# Color_Sensor.net
KiCad netlist of a schematic drawn in Altium Designer
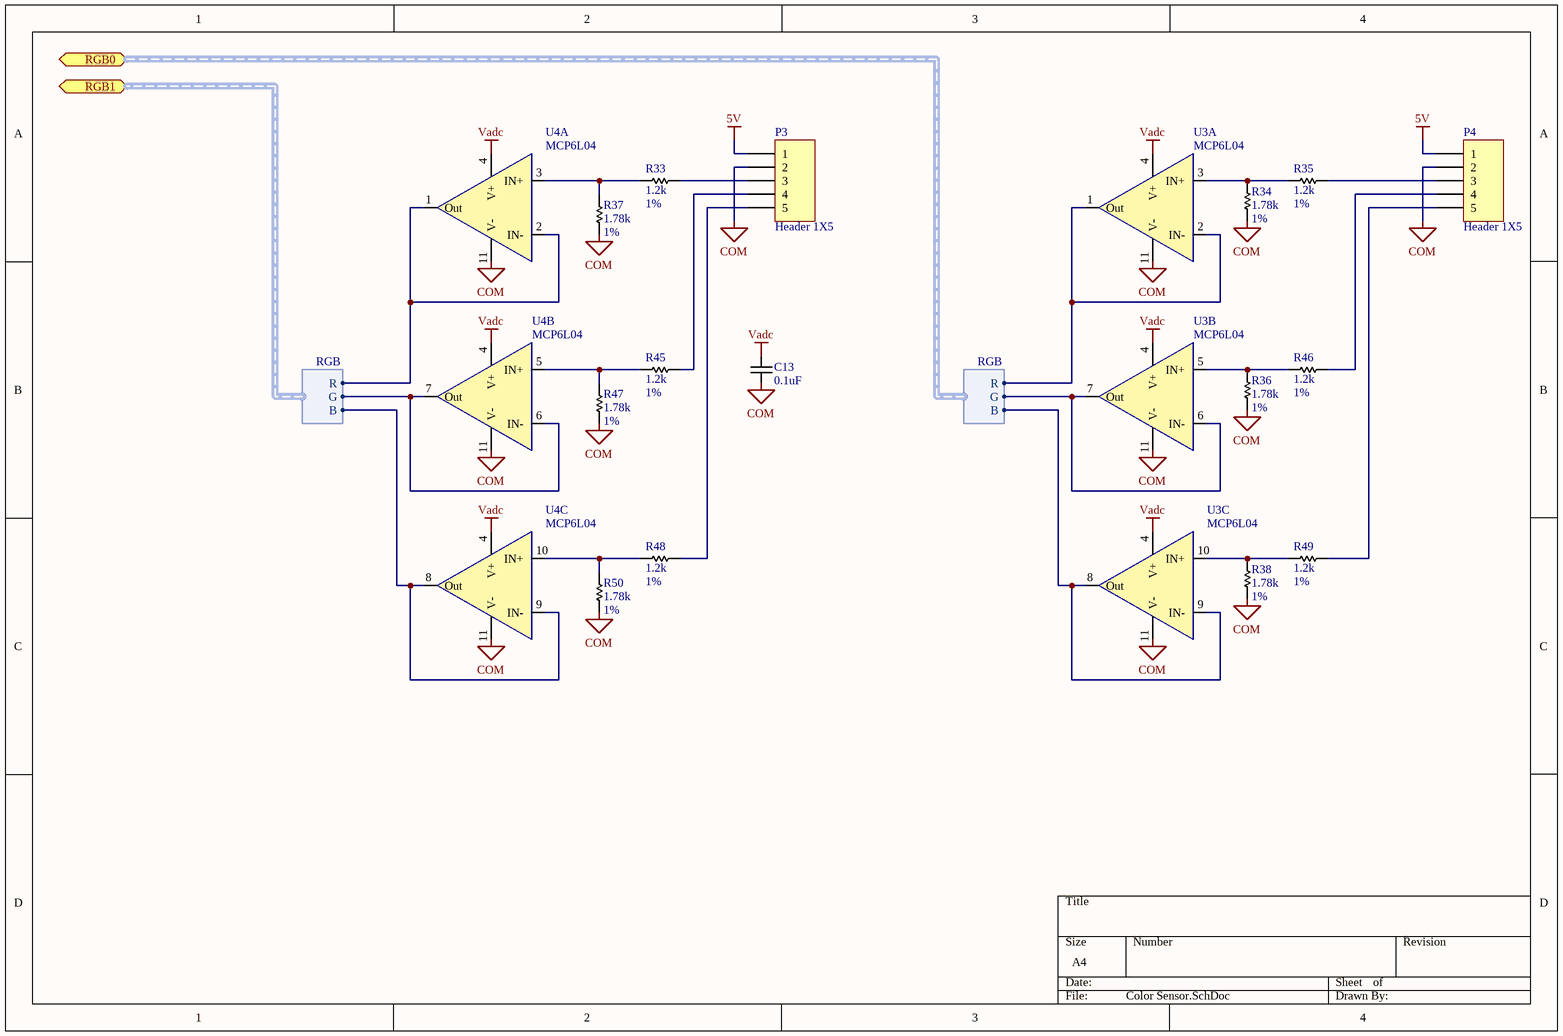
[diagram p0: Color Sensor.SchDoc]

(export (version "E")
  (design (tool "Eeschema 10.0.6"))
  (components
    (comp (ref "C13")
      (value "0.1uF")
      (footprint "0805 - Cap Non-Polarized")
      (description "CAP CER 0.1UF 100V 10% X7R 0805")
      (fields
        (field (name "PART NUMBER") "Cap-TDK-CGA-0.1uF-0805")
        (field (name "MANUFACTURER") "TDK")
        (field (name "CREATED BY") "Pier-Yves")
      )
      (libsource (lib "local") (part "Cap"))
    )
    (comp (ref "P3")
      (value "Header 1X5")
      (footprint "Headers - 1x5 - Vertical - Lock")
      (description "CONN HEADER 5POS .100\" STR TIN")
      (fields
        (field (name "PART NUMBER") "Header-0.100-Vertical-Lock-1X5")
        (field (name "MANUFACTURER") "Molex Inc")
        (field (name "PUBLISHER") "Altium Limited")
        (field (name "CREATED BY") "Pier-Yves")
      )
      (libsource (lib "local") (part "Header 1X5"))
    )
    (comp (ref "P4")
      (value "Header 1X5")
      (footprint "Headers - 1x5 - Vertical - Lock")
      (description "CONN HEADER 5POS .100\" STR TIN")
      (fields
        (field (name "PART NUMBER") "Header-0.100-Vertical-Lock-1X5")
        (field (name "MANUFACTURER") "Molex Inc")
        (field (name "PUBLISHER") "Altium Limited")
        (field (name "CREATED BY") "Pier-Yves")
      )
      (libsource (lib "local") (part "Header 1X5"))
    )
    (comp (ref "R33")
      (value "1.2k")
      (footprint "0805 - Resistor")
      (description "RES 1.20K OHM 1/8W 1% 0805 SMD")
      (fields
        (field (name "PART NUMBER") "Yagao-RC0805-1%-1.2k")
        (field (name "MANUFACTURER") "Yagao")
        (field (name "TOLERANCE") "1%")
        (field (name "CREATED BY") "Pier-Yves")
      )
      (libsource (lib "local") (part "Res"))
    )
    (comp (ref "R34")
      (value "1.78k")
      (footprint "0805 - Resistor")
      (description "RES 1.78K OHM 1/8W 1% 0805 SMD")
      (fields
        (field (name "PART NUMBER") "Yagao-RC0805-1%-1.78k")
        (field (name "MANUFACTURER") "Yagao")
        (field (name "TOLERANCE") "1%")
        (field (name "CREATED BY") "Pier-Yves")
      )
      (libsource (lib "local") (part "Res"))
    )
    (comp (ref "R35")
      (value "1.2k")
      (footprint "0805 - Resistor")
      (description "RES 1.20K OHM 1/8W 1% 0805 SMD")
      (fields
        (field (name "PART NUMBER") "Yagao-RC0805-1%-1.2k")
        (field (name "MANUFACTURER") "Yagao")
        (field (name "TOLERANCE") "1%")
        (field (name "CREATED BY") "Pier-Yves")
      )
      (libsource (lib "local") (part "Res"))
    )
    (comp (ref "R36")
      (value "1.78k")
      (footprint "0805 - Resistor")
      (description "RES 1.78K OHM 1/8W 1% 0805 SMD")
      (fields
        (field (name "PART NUMBER") "Yagao-RC0805-1%-1.78k")
        (field (name "MANUFACTURER") "Yagao")
        (field (name "TOLERANCE") "1%")
        (field (name "CREATED BY") "Pier-Yves")
      )
      (libsource (lib "local") (part "Res"))
    )
    (comp (ref "R37")
      (value "1.78k")
      (footprint "0805 - Resistor")
      (description "RES 1.78K OHM 1/8W 1% 0805 SMD")
      (fields
        (field (name "PART NUMBER") "Yagao-RC0805-1%-1.78k")
        (field (name "MANUFACTURER") "Yagao")
        (field (name "TOLERANCE") "1%")
        (field (name "CREATED BY") "Pier-Yves")
      )
      (libsource (lib "local") (part "Res"))
    )
    (comp (ref "R38")
      (value "1.78k")
      (footprint "0805 - Resistor")
      (description "RES 1.78K OHM 1/8W 1% 0805 SMD")
      (fields
        (field (name "PART NUMBER") "Yagao-RC0805-1%-1.78k")
        (field (name "MANUFACTURER") "Yagao")
        (field (name "TOLERANCE") "1%")
        (field (name "CREATED BY") "Pier-Yves")
      )
      (libsource (lib "local") (part "Res"))
    )
    (comp (ref "R45")
      (value "1.2k")
      (footprint "0805 - Resistor")
      (description "RES 1.20K OHM 1/8W 1% 0805 SMD")
      (fields
        (field (name "PART NUMBER") "Yagao-RC0805-1%-1.2k")
        (field (name "MANUFACTURER") "Yagao")
        (field (name "TOLERANCE") "1%")
        (field (name "CREATED BY") "Pier-Yves")
      )
      (libsource (lib "local") (part "Res"))
    )
    (comp (ref "R46")
      (value "1.2k")
      (footprint "0805 - Resistor")
      (description "RES 1.20K OHM 1/8W 1% 0805 SMD")
      (fields
        (field (name "PART NUMBER") "Yagao-RC0805-1%-1.2k")
        (field (name "MANUFACTURER") "Yagao")
        (field (name "TOLERANCE") "1%")
        (field (name "CREATED BY") "Pier-Yves")
      )
      (libsource (lib "local") (part "Res"))
    )
    (comp (ref "R47")
      (value "1.78k")
      (footprint "0805 - Resistor")
      (description "RES 1.78K OHM 1/8W 1% 0805 SMD")
      (fields
        (field (name "PART NUMBER") "Yagao-RC0805-1%-1.78k")
        (field (name "MANUFACTURER") "Yagao")
        (field (name "TOLERANCE") "1%")
        (field (name "CREATED BY") "Pier-Yves")
      )
      (libsource (lib "local") (part "Res"))
    )
    (comp (ref "R48")
      (value "1.2k")
      (footprint "0805 - Resistor")
      (description "RES 1.20K OHM 1/8W 1% 0805 SMD")
      (fields
        (field (name "PART NUMBER") "Yagao-RC0805-1%-1.2k")
        (field (name "MANUFACTURER") "Yagao")
        (field (name "TOLERANCE") "1%")
        (field (name "CREATED BY") "Pier-Yves")
      )
      (libsource (lib "local") (part "Res"))
    )
    (comp (ref "R49")
      (value "1.2k")
      (footprint "0805 - Resistor")
      (description "RES 1.20K OHM 1/8W 1% 0805 SMD")
      (fields
        (field (name "PART NUMBER") "Yagao-RC0805-1%-1.2k")
        (field (name "MANUFACTURER") "Yagao")
        (field (name "TOLERANCE") "1%")
        (field (name "CREATED BY") "Pier-Yves")
      )
      (libsource (lib "local") (part "Res"))
    )
    (comp (ref "R50")
      (value "1.78k")
      (footprint "0805 - Resistor")
      (description "RES 1.78K OHM 1/8W 1% 0805 SMD")
      (fields
        (field (name "PART NUMBER") "Yagao-RC0805-1%-1.78k")
        (field (name "MANUFACTURER") "Yagao")
        (field (name "TOLERANCE") "1%")
        (field (name "CREATED BY") "Pier-Yves")
      )
      (libsource (lib "local") (part "Res"))
    )
    (comp (ref "U3")
      (value "MCP6L04")
      (footprint "SOIC14 - 0.150")
      (description "IC OPAMP GP 1MHZ RRO 14SOIC")
      (fields
        (field (name "PART NUMBER") "MCP6L04T")
        (field (name "MANUFACTURER") "Microchip")
        (field (name "CREATED BY") "Pier-Yves")
      )
      (libsource (lib "local") (part "MCP6L04"))
    )
    (comp (ref "U4")
      (value "MCP6L04")
      (footprint "SOIC14 - 0.150")
      (description "IC OPAMP GP 1MHZ RRO 14SOIC")
      (fields
        (field (name "PART NUMBER") "MCP6L04T")
        (field (name "MANUFACTURER") "Microchip")
        (field (name "CREATED BY") "Pier-Yves")
      )
      (libsource (lib "local") (part "MCP6L04"))
    )
  )
  (nets
    (net (code "3") (name "5V") (class "Default")
      (node (ref "P3") (pin "1") (pinfunction "1_1") (pintype "passive"))
      (node (ref "P4") (pin "1") (pinfunction "1_1") (pintype "passive"))
    )
    (net (code "4") (name "COM") (class "Default")
      (node (ref "C13") (pin "2") (pinfunction "2_2") (pintype "passive"))
      (node (ref "P3") (pin "2") (pinfunction "2_2") (pintype "passive"))
      (node (ref "P4") (pin "2") (pinfunction "2_2") (pintype "passive"))
      (node (ref "R34") (pin "2") (pinfunction "2_2") (pintype "passive"))
      (node (ref "R36") (pin "2") (pinfunction "2_2") (pintype "passive"))
      (node (ref "R37") (pin "2") (pinfunction "2_2") (pintype "passive"))
      (node (ref "R38") (pin "2") (pinfunction "2_2") (pintype "passive"))
      (node (ref "R47") (pin "2") (pinfunction "2_2") (pintype "passive"))
      (node (ref "R50") (pin "2") (pinfunction "2_2") (pintype "passive"))
      (node (ref "U3") (pin "11") (pinfunction "V-_11") (pintype "power_in"))
      (node (ref "U4") (pin "11") (pinfunction "V-_11") (pintype "power_in"))
    )
    (net (code "5") (name "Net-(P3-Pad3)") (class "Default")
      (node (ref "P3") (pin "3") (pinfunction "3_3") (pintype "passive"))
      (node (ref "R33") (pin "1") (pinfunction "1_1") (pintype "passive"))
    )
    (net (code "6") (name "Net-(P3-Pad4)") (class "Default")
      (node (ref "P3") (pin "4") (pinfunction "4_4") (pintype "passive"))
      (node (ref "R45") (pin "1") (pinfunction "1_1") (pintype "passive"))
    )
    (net (code "7") (name "Net-(P3-Pad5)") (class "Default")
      (node (ref "P3") (pin "5") (pinfunction "5_5") (pintype "passive"))
      (node (ref "R48") (pin "1") (pinfunction "1_1") (pintype "passive"))
    )
    (net (code "8") (name "Net-(P4-Pad3)") (class "Default")
      (node (ref "P4") (pin "3") (pinfunction "3_3") (pintype "passive"))
      (node (ref "R35") (pin "1") (pinfunction "1_1") (pintype "passive"))
    )
    (net (code "9") (name "Net-(P4-Pad4)") (class "Default")
      (node (ref "P4") (pin "4") (pinfunction "4_4") (pintype "passive"))
      (node (ref "R46") (pin "1") (pinfunction "1_1") (pintype "passive"))
    )
    (net (code "10") (name "Net-(P4-Pad5)") (class "Default")
      (node (ref "P4") (pin "5") (pinfunction "5_5") (pintype "passive"))
      (node (ref "R49") (pin "1") (pinfunction "1_1") (pintype "passive"))
    )
    (net (code "11") (name "Net-(U3A-IN+)") (class "Default")
      (node (ref "R34") (pin "1") (pinfunction "1_1") (pintype "passive"))
      (node (ref "R35") (pin "2") (pinfunction "2_2") (pintype "passive"))
      (node (ref "U3") (pin "3") (pinfunction "IN+_3") (pintype "passive"))
    )
    (net (code "12") (name "Net-(U3A-IN-)") (class "Default")
      (node (ref "U3") (pin "1") (pinfunction "Out_1") (pintype "passive"))
      (node (ref "U3") (pin "2") (pinfunction "IN-_2") (pintype "passive"))
    )
    (net (code "13") (name "Net-(U3B-IN+)") (class "Default")
      (node (ref "R36") (pin "1") (pinfunction "1_1") (pintype "passive"))
      (node (ref "R46") (pin "2") (pinfunction "2_2") (pintype "passive"))
      (node (ref "U3") (pin "5") (pinfunction "IN+_5") (pintype "passive"))
    )
    (net (code "14") (name "Net-(U3B-IN-)") (class "Default")
      (node (ref "U3") (pin "6") (pinfunction "IN-_6") (pintype "passive"))
      (node (ref "U3") (pin "7") (pinfunction "Out_7") (pintype "passive"))
    )
    (net (code "15") (name "Net-(U3C-IN+)") (class "Default")
      (node (ref "R38") (pin "1") (pinfunction "1_1") (pintype "passive"))
      (node (ref "R49") (pin "2") (pinfunction "2_2") (pintype "passive"))
      (node (ref "U3") (pin "10") (pinfunction "IN+_10") (pintype "passive"))
    )
    (net (code "16") (name "Net-(U3C-IN-)") (class "Default")
      (node (ref "U3") (pin "8") (pinfunction "Out_8") (pintype "passive"))
      (node (ref "U3") (pin "9") (pinfunction "IN-_9") (pintype "passive"))
    )
    (net (code "17") (name "Net-(U4A-IN+)") (class "Default")
      (node (ref "R33") (pin "2") (pinfunction "2_2") (pintype "passive"))
      (node (ref "R37") (pin "1") (pinfunction "1_1") (pintype "passive"))
      (node (ref "U4") (pin "3") (pinfunction "IN+_3") (pintype "passive"))
    )
    (net (code "18") (name "Net-(U4A-IN-)") (class "Default")
      (node (ref "U4") (pin "1") (pinfunction "Out_1") (pintype "passive"))
      (node (ref "U4") (pin "2") (pinfunction "IN-_2") (pintype "passive"))
    )
    (net (code "19") (name "Net-(U4B-IN+)") (class "Default")
      (node (ref "R45") (pin "2") (pinfunction "2_2") (pintype "passive"))
      (node (ref "R47") (pin "1") (pinfunction "1_1") (pintype "passive"))
      (node (ref "U4") (pin "5") (pinfunction "IN+_5") (pintype "passive"))
    )
    (net (code "20") (name "Net-(U4B-IN-)") (class "Default")
      (node (ref "U4") (pin "6") (pinfunction "IN-_6") (pintype "passive"))
      (node (ref "U4") (pin "7") (pinfunction "Out_7") (pintype "passive"))
    )
    (net (code "21") (name "Net-(U4C-IN+)") (class "Default")
      (node (ref "R48") (pin "2") (pinfunction "2_2") (pintype "passive"))
      (node (ref "R50") (pin "1") (pinfunction "1_1") (pintype "passive"))
      (node (ref "U4") (pin "10") (pinfunction "IN+_10") (pintype "passive"))
    )
    (net (code "22") (name "Net-(U4C-IN-)") (class "Default")
      (node (ref "U4") (pin "8") (pinfunction "Out_8") (pintype "passive"))
      (node (ref "U4") (pin "9") (pinfunction "IN-_9") (pintype "passive"))
    )
    (net (code "23") (name "Vadc") (class "Default")
      (node (ref "C13") (pin "1") (pinfunction "1_1") (pintype "passive"))
      (node (ref "U3") (pin "4") (pinfunction "V+_4") (pintype "power_in"))
      (node (ref "U4") (pin "4") (pinfunction "V+_4") (pintype "power_in"))
    )
  )
)
